# CPU.net
KiCad netlist of a schematic drawn in Altium Designer
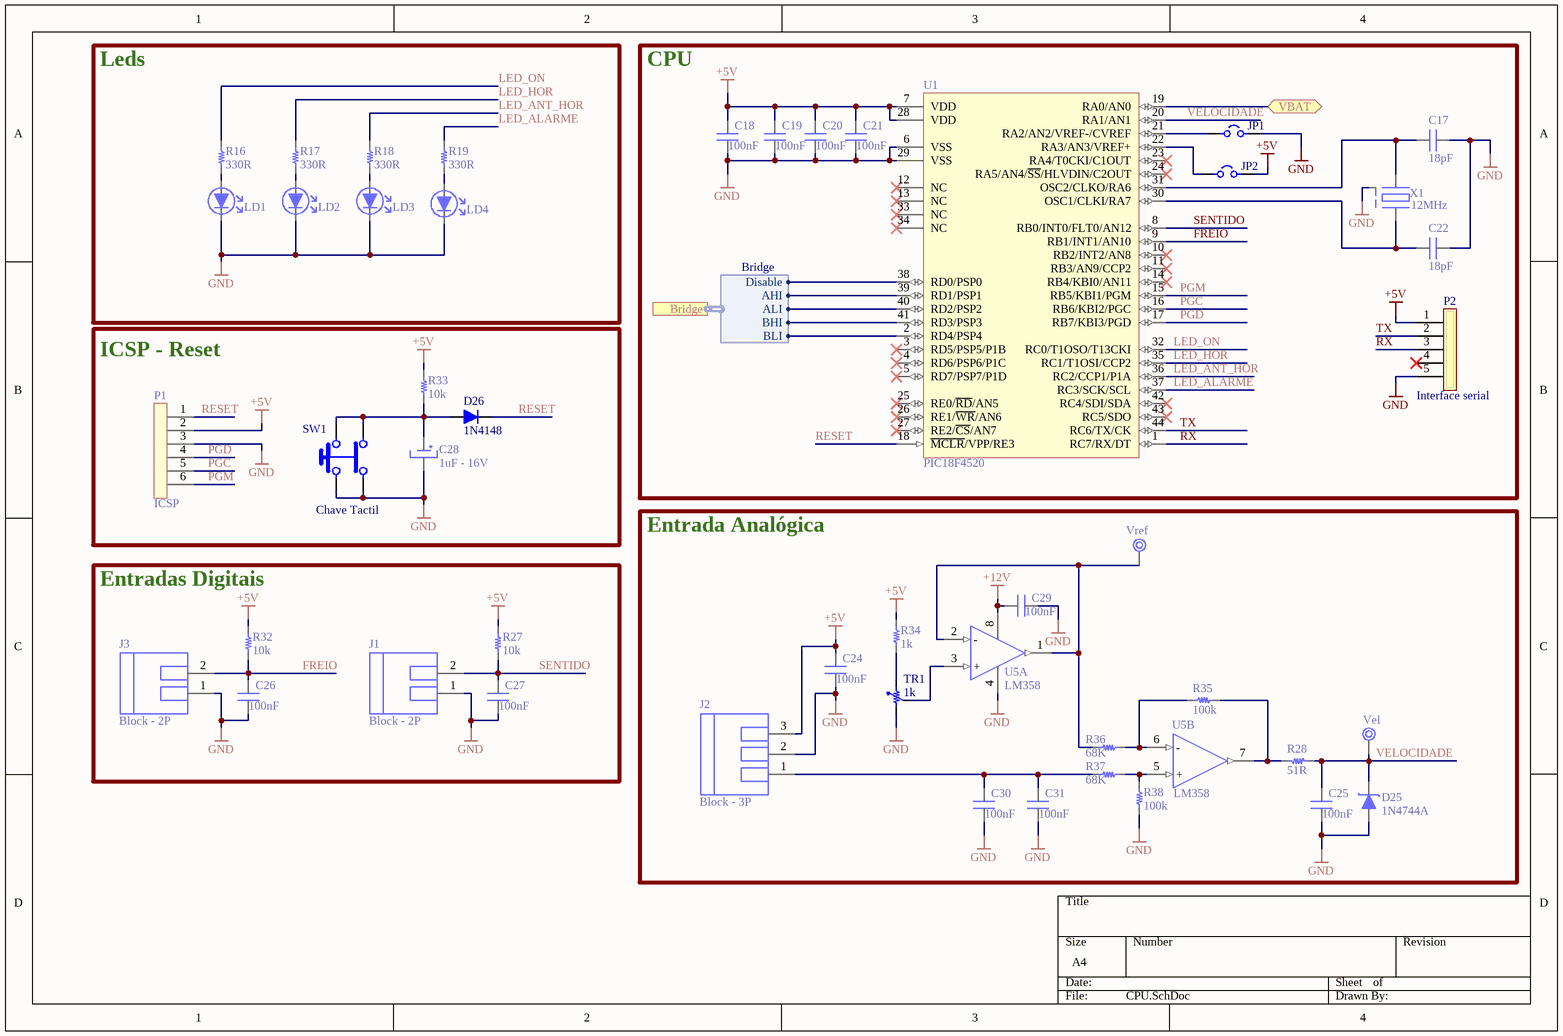
[diagram p0: CPU.SchDoc]

(export (version "E")
  (design (tool "Eeschema 10.0.6"))
  (components
    (comp (ref "C17")
      (value "18pF")
      (footprint "Capacitor_0805")
      (description "Capacitor C0805 18pF")
      (libsource (lib "bike") (part "Cap0805_100nF"))
    )
    (comp (ref "C18")
      (value "100nF")
      (footprint "Capacitor_0805")
      (description "Capacitor C0805 100nF Desacoplamento")
      (libsource (lib "bike") (part "Cap0805_100nF"))
    )
    (comp (ref "C19")
      (value "100nF")
      (footprint "Capacitor_0805")
      (description "Capacitor C0805 100nF Desacoplamento")
      (libsource (lib "bike") (part "Cap0805_100nF"))
    )
    (comp (ref "C20")
      (value "100nF")
      (footprint "Capacitor_0805")
      (description "Capacitor C0805 100nF Desacoplamento")
      (libsource (lib "bike") (part "Cap0805_100nF"))
    )
    (comp (ref "C21")
      (value "100nF")
      (footprint "Capacitor_0805")
      (description "Capacitor C0805 100nF Desacoplamento")
      (libsource (lib "bike") (part "Cap0805_100nF"))
    )
    (comp (ref "C22")
      (value "18pF")
      (footprint "Capacitor_0805")
      (description "Capacitor C0805 18pF")
      (libsource (lib "bike") (part "Cap0805_100nF"))
    )
    (comp (ref "C24")
      (value "100nF")
      (footprint "Capacitor_0805")
      (description "Capacitor C0805 100nF Desacoplamento")
      (libsource (lib "bike") (part "Cap0805_100nF"))
    )
    (comp (ref "C25")
      (value "100nF")
      (footprint "Capacitor_0805")
      (description "Capacitor C0805 100nF Desacoplamento")
      (libsource (lib "bike") (part "Cap0805_100nF"))
    )
    (comp (ref "C26")
      (value "100nF")
      (footprint "Capacitor_0805")
      (description "Capacitor C0805 100nF Desacoplamento")
      (libsource (lib "bike") (part "Cap0805_100nF"))
    )
    (comp (ref "C27")
      (value "100nF")
      (footprint "Capacitor_0805")
      (description "Capacitor C0805 100nF Desacoplamento")
      (libsource (lib "bike") (part "Cap0805_100nF"))
    )
    (comp (ref "C28")
      (value "1uF - 16V")
      (footprint "CAP_8x5mm")
      (description "Capacitor_1uF_16V")
      (libsource (lib "bike") (part "1uF - 16V"))
    )
    (comp (ref "C29")
      (value "100nF")
      (footprint "Capacitor_0805")
      (description "Capacitor C0805 100nF Desacoplamento")
      (libsource (lib "bike") (part "Cap0805_100nF"))
    )
    (comp (ref "C30")
      (value "100nF")
      (footprint "Capacitor_0805")
      (description "Capacitor C0805 100nF Desacoplamento")
      (libsource (lib "bike") (part "Cap0805_100nF"))
    )
    (comp (ref "C31")
      (value "100nF")
      (footprint "Capacitor_0805")
      (description "Capacitor C0805 100nF Desacoplamento")
      (libsource (lib "bike") (part "Cap0805_100nF"))
    )
    (comp (ref "D25")
      (value "1N4744A")
      (footprint "Diode_PHT")
      (description "Diodo Zener 15V 200mA")
      (libsource (lib "bike") (part "1N4744A"))
    )
    (comp (ref "D26")
      (value "1N4148")
      (footprint "SOD-80")
      (description "Diodo de uso geral")
      (libsource (lib "bike") (part "1N4148"))
    )
    (comp (ref "J1")
      (value "Block - 2P")
      (footprint "CONECTOR_2P_2PARTES")
      (description "Conector block 2 pinos 2 peças")
      (libsource (lib "bike") (part "Block - 2P"))
    )
    (comp (ref "J2")
      (value "Block - 3P")
      (footprint "CONECTOR_3P_2PARTES")
      (description "Conector block 3 pinos 2 peças")
      (libsource (lib "bike") (part "Block - 3P"))
    )
    (comp (ref "J3")
      (value "Block - 2P")
      (footprint "CONECTOR_2P_2PARTES")
      (description "Conector block 2 pinos 2 peças")
      (libsource (lib "bike") (part "Block - 2P"))
    )
    (comp (ref "JP1")
      (value "Jumper")
      (footprint "JUMPER")
      (description "Jumper de solda")
      (libsource (lib "bike") (part "Jumper"))
    )
    (comp (ref "JP2")
      (value "Jumper")
      (footprint "JUMPER")
      (description "Jumper de solda")
      (libsource (lib "bike") (part "Jumper"))
    )
    (comp (ref "LD1")
      (value "Led")
      (footprint "Led 5mm")
      (description "Led padrão PTH ou SMD")
      (libsource (lib "bike") (part "Led"))
    )
    (comp (ref "LD2")
      (value "Led")
      (footprint "Led 5mm")
      (description "Led padrão PTH ou SMD")
      (libsource (lib "bike") (part "Led"))
    )
    (comp (ref "LD3")
      (value "Led")
      (footprint "Led 5mm")
      (description "Led padrão PTH ou SMD")
      (libsource (lib "bike") (part "Led"))
    )
    (comp (ref "LD4")
      (value "Led")
      (footprint "Led 5mm")
      (description "Led padrão PTH ou SMD")
      (libsource (lib "bike") (part "Led"))
    )
    (comp (ref "P1")
      (value "ICSP")
      (footprint "header 1x6")
      (description "Conector ICSP para programação e debugger do PIC")
      (libsource (lib "bike") (part "ICSP"))
    )
    (comp (ref "P2")
      (value "Interface serial")
      (footprint "HEADER 1X5")
      (description "Header 1x5 2.56mm")
      (libsource (lib "bike") (part "Header 1x5"))
    )
    (comp (ref "R16")
      (value "330R")
      (footprint "R_0805")
      (description "Resistor padrão 0805")
      (libsource (lib "bike") (part "Resistor_330R"))
    )
    (comp (ref "R17")
      (value "330R")
      (footprint "R_0805")
      (description "Resistor padrão 0805")
      (libsource (lib "bike") (part "Resistor_330R"))
    )
    (comp (ref "R18")
      (value "330R")
      (footprint "R_0805")
      (description "Resistor padrão 0805")
      (libsource (lib "bike") (part "Resistor_330R"))
    )
    (comp (ref "R19")
      (value "330R")
      (footprint "R_0805")
      (description "Resistor padrão 0805")
      (libsource (lib "bike") (part "Resistor_330R"))
    )
    (comp (ref "R27")
      (value "10k")
      (footprint "R_0805")
      (description "Resistor padrão 0805")
      (libsource (lib "bike") (part "Resistor_10K"))
    )
    (comp (ref "R28")
      (value "51R")
      (footprint "R_0805")
      (description "Resistor padrão 0805")
      (libsource (lib "bike") (part "Resistor_10K"))
    )
    (comp (ref "R32")
      (value "10k")
      (footprint "R_0805")
      (description "Resistor padrão 0805")
      (libsource (lib "bike") (part "Resistor_10K"))
    )
    (comp (ref "R33")
      (value "10k")
      (footprint "R_0805")
      (description "Resistor padrão 0805")
      (libsource (lib "bike") (part "Resistor_10K"))
    )
    (comp (ref "R34")
      (value "1k")
      (footprint "R_0805")
      (description "Resistor padrão 0805")
      (libsource (lib "bike") (part "Resistor_10K"))
    )
    (comp (ref "R35")
      (value "100k")
      (footprint "R_0805")
      (description "Resistor padrão 0805")
      (libsource (lib "bike") (part "Resistor_10K"))
    )
    (comp (ref "R36")
      (value "68K")
      (footprint "R_0805")
      (description "Resistor padrão 0805")
      (libsource (lib "bike") (part "Resistor_10K"))
    )
    (comp (ref "R37")
      (value "68K")
      (footprint "R_0805")
      (description "Resistor padrão 0805")
      (libsource (lib "bike") (part "Resistor_10K"))
    )
    (comp (ref "R38")
      (value "100k")
      (footprint "R_0805")
      (description "Resistor padrão 0805")
      (libsource (lib "bike") (part "Resistor_10K"))
    )
    (comp (ref "SW1")
      (value "Chave Tactil")
      (footprint "CHAVE TACTIL")
      (description "Chave tactil")
      (libsource (lib "bike") (part "Chave Tactil"))
    )
    (comp (ref "TR1")
      (value "1k")
      (footprint "Trimpot")
      (description "Trimpot 1k")
      (libsource (lib "bike") (part "Trimpot"))
    )
    (comp (ref "U1")
      (value "PIC18F4520")
      (footprint "TQFP-PT44")
      (description "Microcontrolador de 8 bits da família PIC")
      (libsource (lib "bike") (part "PIC18F4520"))
    )
    (comp (ref "U5")
      (value "LM358")
      (footprint "SOP8")
      (description "LMx58-N Low-Power, Dual-Operational Amplifiers")
      (libsource (lib "bike") (part "LM358"))
    )
    (comp (ref "Vel") (value "+12V") (footprint "TEST_POINT") (libsource (lib "bike") (part "test_point")))
    (comp (ref "Vref") (value "+12V") (footprint "TEST_POINT") (libsource (lib "bike") (part "test_point")))
    (comp (ref "X1")
      (value "12MHz")
      (footprint "Crystal_3Pins - 4,98mm")
      (description "Crystal Genérico")
      (libsource (lib "bike") (part "Crystal"))
    )
  )
  (nets
    (net (code "2") (name "+5V") (class "Default")
      (node (ref "C18") (pin "2") (pinfunction "2_2") (pintype "passive"))
      (node (ref "C19") (pin "2") (pinfunction "2_2") (pintype "passive"))
      (node (ref "C20") (pin "2") (pinfunction "2_2") (pintype "passive"))
      (node (ref "C21") (pin "2") (pinfunction "2_2") (pintype "passive"))
      (node (ref "C24") (pin "2") (pinfunction "2_2") (pintype "passive"))
      (node (ref "J2") (pin "3") (pinfunction "3_3") (pintype "passive"))
      (node (ref "JP2") (pin "2") (pinfunction "2_2") (pintype "passive"))
      (node (ref "P1") (pin "2") (pinfunction "2_2") (pintype "passive"))
      (node (ref "P2") (pin "1") (pinfunction "1_1") (pintype "passive"))
      (node (ref "R27") (pin "2") (pinfunction "2_2") (pintype "passive"))
      (node (ref "R32") (pin "2") (pinfunction "2_2") (pintype "passive"))
      (node (ref "R33") (pin "2") (pinfunction "2_2") (pintype "passive"))
      (node (ref "R34") (pin "1") (pinfunction "1_1") (pintype "passive"))
      (node (ref "U1") (pin "28") (pinfunction "VDD_28") (pintype "power_in"))
      (node (ref "U1") (pin "7") (pinfunction "VDD_7") (pintype "power_in"))
    )
    (net (code "3") (name "+12V") (class "Default")
      (node (ref "C29") (pin "2") (pinfunction "2_2") (pintype "passive"))
      (node (ref "U5") (pin "8") (pinfunction "VCC_8") (pintype "passive"))
    )
    (net (code "4") (name "/AHI") (class "Default")
      (node (ref "U1") (pin "39") (pinfunction "RD1/PSP1_39") (pintype "bidirectional"))
    )
    (net (code "5") (name "/ALI") (class "Default")
      (node (ref "U1") (pin "40") (pinfunction "RD2/PSP2_40") (pintype "bidirectional"))
    )
    (net (code "6") (name "/BHI") (class "Default")
      (node (ref "U1") (pin "41") (pinfunction "RD3/PSP3_41") (pintype "bidirectional"))
    )
    (net (code "7") (name "/BLI") (class "Default")
      (node (ref "U1") (pin "2") (pinfunction "RD4/PSP4_2") (pintype "bidirectional"))
    )
    (net (code "8") (name "/Disable") (class "Default")
      (node (ref "U1") (pin "38") (pinfunction "RD0/PSP0_38") (pintype "bidirectional"))
    )
    (net (code "9") (name "/FREIO") (class "Default")
      (node (ref "C26") (pin "2") (pinfunction "2_2") (pintype "passive"))
      (node (ref "J3") (pin "2") (pinfunction "4_2") (pintype "passive"))
      (node (ref "R32") (pin "1") (pinfunction "1_1") (pintype "passive"))
      (node (ref "U1") (pin "9") (pinfunction "RB1/INT1/AN10_9") (pintype "bidirectional"))
    )
    (net (code "10") (name "/LED_ALARME") (class "Default")
      (node (ref "R19") (pin "2") (pinfunction "2_2") (pintype "passive"))
      (node (ref "U1") (pin "37") (pinfunction "RC3/SCK/SCL_37") (pintype "bidirectional"))
    )
    (net (code "11") (name "/LED_ANT_HOR") (class "Default")
      (node (ref "R18") (pin "2") (pinfunction "2_2") (pintype "passive"))
      (node (ref "U1") (pin "36") (pinfunction "RC2/CCP1/P1A_36") (pintype "bidirectional"))
    )
    (net (code "12") (name "/LED_HOR") (class "Default")
      (node (ref "R17") (pin "2") (pinfunction "2_2") (pintype "passive"))
      (node (ref "U1") (pin "35") (pinfunction "RC1/T1OSI/CCP2_35") (pintype "bidirectional"))
    )
    (net (code "13") (name "/LED_ON") (class "Default")
      (node (ref "R16") (pin "2") (pinfunction "2_2") (pintype "passive"))
      (node (ref "U1") (pin "32") (pinfunction "RC0/T1OSO/T13CKI_32") (pintype "bidirectional"))
    )
    (net (code "14") (name "/PGC") (class "Default")
      (node (ref "P1") (pin "5") (pinfunction "5_5") (pintype "passive"))
      (node (ref "U1") (pin "16") (pinfunction "RB6/KBI2/PGC_16") (pintype "bidirectional"))
    )
    (net (code "15") (name "/PGD") (class "Default")
      (node (ref "P1") (pin "4") (pinfunction "4_4") (pintype "passive"))
      (node (ref "U1") (pin "17") (pinfunction "RB7/KBI3/PGD_17") (pintype "bidirectional"))
    )
    (net (code "16") (name "/PGM") (class "Default")
      (node (ref "P1") (pin "6") (pinfunction "6_6") (pintype "passive"))
      (node (ref "U1") (pin "15") (pinfunction "RB5/KBI1/PGM_15") (pintype "bidirectional"))
    )
    (net (code "17") (name "/RESET") (class "Default")
      (node (ref "D26") (pin "1") (pinfunction "Catodo_1") (pintype "passive"))
      (node (ref "P1") (pin "1") (pinfunction "1_1") (pintype "passive"))
      (node (ref "U1") (pin "18") (pinfunction "~{MCLR}/VPP/RE3_18") (pintype "input"))
    )
    (net (code "18") (name "/RX") (class "Default")
      (node (ref "P2") (pin "3") (pinfunction "3_3") (pintype "passive"))
      (node (ref "U1") (pin "1") (pinfunction "RC7/RX/DT_1") (pintype "bidirectional"))
    )
    (net (code "19") (name "/SENTIDO") (class "Default")
      (node (ref "C27") (pin "2") (pinfunction "2_2") (pintype "passive"))
      (node (ref "J1") (pin "2") (pinfunction "4_2") (pintype "passive"))
      (node (ref "R27") (pin "1") (pinfunction "1_1") (pintype "passive"))
      (node (ref "U1") (pin "8") (pinfunction "RB0/INT0/FLT0/AN12_8") (pintype "bidirectional"))
    )
    (net (code "20") (name "/TX") (class "Default")
      (node (ref "P2") (pin "2") (pinfunction "2_2") (pintype "passive"))
      (node (ref "U1") (pin "44") (pinfunction "RC6/TX/CK_44") (pintype "bidirectional"))
    )
    (net (code "21") (name "/VBAT") (class "Default")
      (node (ref "U1") (pin "19") (pinfunction "RA0/AN0_19") (pintype "bidirectional"))
    )
    (net (code "22") (name "/VELOCIDADE") (class "Default")
      (node (ref "C25") (pin "2") (pinfunction "2_2") (pintype "passive"))
      (node (ref "D25") (pin "K") (pinfunction "Catodo_K") (pintype "passive"))
      (node (ref "R28") (pin "2") (pinfunction "2_2") (pintype "passive"))
      (node (ref "U1") (pin "20") (pinfunction "RA1/AN1_20") (pintype "bidirectional"))
      (node (ref "Vel") (pin "1") (pinfunction "1_1") (pintype "passive"))
    )
    (net (code "24") (name "GND") (class "Default")
      (node (ref "C17") (pin "1") (pinfunction "1_1") (pintype "passive"))
      (node (ref "C18") (pin "1") (pinfunction "1_1") (pintype "passive"))
      (node (ref "C19") (pin "1") (pinfunction "1_1") (pintype "passive"))
      (node (ref "C20") (pin "1") (pinfunction "1_1") (pintype "passive"))
      (node (ref "C21") (pin "1") (pinfunction "1_1") (pintype "passive"))
      (node (ref "C22") (pin "1") (pinfunction "1_1") (pintype "passive"))
      (node (ref "C24") (pin "1") (pinfunction "1_1") (pintype "passive"))
      (node (ref "C25") (pin "1") (pinfunction "1_1") (pintype "passive"))
      (node (ref "C26") (pin "1") (pinfunction "1_1") (pintype "passive"))
      (node (ref "C27") (pin "1") (pinfunction "1_1") (pintype "passive"))
      (node (ref "C28") (pin "2") (pinfunction "2_2") (pintype "passive"))
      (node (ref "C29") (pin "1") (pinfunction "1_1") (pintype "passive"))
      (node (ref "C30") (pin "1") (pinfunction "1_1") (pintype "passive"))
      (node (ref "C31") (pin "1") (pinfunction "1_1") (pintype "passive"))
      (node (ref "D25") (pin "A") (pinfunction "Anodo_A") (pintype "passive"))
      (node (ref "J1") (pin "1") (pinfunction "5_1") (pintype "passive"))
      (node (ref "J2") (pin "2") (pinfunction "4_2") (pintype "passive"))
      (node (ref "J3") (pin "1") (pinfunction "5_1") (pintype "passive"))
      (node (ref "JP1") (pin "2") (pinfunction "2_2") (pintype "passive"))
      (node (ref "LD1") (pin "1") (pinfunction "Catodo_1") (pintype "passive"))
      (node (ref "LD2") (pin "1") (pinfunction "Catodo_1") (pintype "passive"))
      (node (ref "LD3") (pin "1") (pinfunction "Catodo_1") (pintype "passive"))
      (node (ref "LD4") (pin "1") (pinfunction "Catodo_1") (pintype "passive"))
      (node (ref "P1") (pin "3") (pinfunction "3_3") (pintype "passive"))
      (node (ref "P2") (pin "5") (pinfunction "5_5") (pintype "passive"))
      (node (ref "R38") (pin "1") (pinfunction "1_1") (pintype "passive"))
      (node (ref "SW1") (pin "1") (pinfunction "1_1") (pintype "passive"))
      (node (ref "SW1") (pin "2") (pinfunction "2_2") (pintype "passive"))
      (node (ref "TR1") (pin "3") (pinfunction "3_3") (pintype "passive"))
      (node (ref "U1") (pin "29") (pinfunction "VSS_29") (pintype "power_in"))
      (node (ref "U1") (pin "6") (pinfunction "VSS_6") (pintype "power_in"))
      (node (ref "U5") (pin "4") (pinfunction "VDD_4") (pintype "passive"))
      (node (ref "X1") (pin "3") (pinfunction "GND_3") (pintype "passive"))
    )
    (net (code "25") (name "Net-(D26-Anodo)") (class "Default")
      (node (ref "C28") (pin "1") (pinfunction "1_1") (pintype "passive"))
      (node (ref "D26") (pin "2") (pinfunction "Anodo_2") (pintype "passive"))
      (node (ref "R33") (pin "1") (pinfunction "1_1") (pintype "passive"))
      (node (ref "SW1") (pin "3") (pinfunction "3_3") (pintype "passive"))
      (node (ref "SW1") (pin "4") (pinfunction "4_4") (pintype "passive"))
    )
    (net (code "26") (name "Net-(J2-5)") (class "Default")
      (node (ref "C30") (pin "2") (pinfunction "2_2") (pintype "passive"))
      (node (ref "C31") (pin "2") (pinfunction "2_2") (pintype "passive"))
      (node (ref "J2") (pin "1") (pinfunction "5_1") (pintype "passive"))
      (node (ref "R37") (pin "2") (pinfunction "2_2") (pintype "passive"))
    )
    (net (code "27") (name "Net-(LD1-Anodo)") (class "Default")
      (node (ref "LD1") (pin "2") (pinfunction "Anodo_2") (pintype "passive"))
      (node (ref "R16") (pin "1") (pinfunction "1_1") (pintype "passive"))
    )
    (net (code "28") (name "Net-(LD2-Anodo)") (class "Default")
      (node (ref "LD2") (pin "2") (pinfunction "Anodo_2") (pintype "passive"))
      (node (ref "R17") (pin "1") (pinfunction "1_1") (pintype "passive"))
    )
    (net (code "29") (name "Net-(LD3-Anodo)") (class "Default")
      (node (ref "LD3") (pin "2") (pinfunction "Anodo_2") (pintype "passive"))
      (node (ref "R18") (pin "1") (pinfunction "1_1") (pintype "passive"))
    )
    (net (code "30") (name "Net-(LD4-Anodo)") (class "Default")
      (node (ref "LD4") (pin "2") (pinfunction "Anodo_2") (pintype "passive"))
      (node (ref "R19") (pin "1") (pinfunction "1_1") (pintype "passive"))
    )
    (net (code "31") (name "Net-(R34-Pad2)") (class "Default")
      (node (ref "R34") (pin "2") (pinfunction "2_2") (pintype "passive"))
      (node (ref "TR1") (pin "1") (pinfunction "1_1") (pintype "passive"))
    )
    (net (code "32") (name "Net-(U1-OSC1{slash}CLKI{slash}RA7)") (class "Default")
      (node (ref "C22") (pin "2") (pinfunction "2_2") (pintype "passive"))
      (node (ref "U1") (pin "30") (pinfunction "OSC1/CLKI/RA7_30") (pintype "bidirectional"))
      (node (ref "X1") (pin "2") (pinfunction "2_2") (pintype "passive"))
    )
    (net (code "33") (name "Net-(U1-OSC2{slash}CLKO{slash}RA6)") (class "Default")
      (node (ref "C17") (pin "2") (pinfunction "2_2") (pintype "passive"))
      (node (ref "U1") (pin "31") (pinfunction "OSC2/CLKO/RA6_31") (pintype "bidirectional"))
      (node (ref "X1") (pin "1") (pinfunction "1_1") (pintype "passive"))
    )
    (net (code "34") (name "Net-(U1-RA2{slash}AN2{slash}VREF-{slash}CVREF)") (class "Default")
      (node (ref "JP1") (pin "1") (pinfunction "1_1") (pintype "passive"))
      (node (ref "U1") (pin "21") (pinfunction "RA2/AN2/VREF-/CVREF_21") (pintype "bidirectional"))
    )
    (net (code "35") (name "Net-(U1-RA3{slash}AN3{slash}VREF+)") (class "Default")
      (node (ref "JP2") (pin "1") (pinfunction "1_1") (pintype "passive"))
      (node (ref "U1") (pin "22") (pinfunction "RA3/AN3/VREF+_22") (pintype "bidirectional"))
    )
    (net (code "36") (name "Net-(U5A-+)") (class "Default")
      (node (ref "TR1") (pin "2") (pinfunction "2_2") (pintype "passive"))
      (node (ref "U5") (pin "3") (pinfunction "+_3") (pintype "input"))
    )
    (net (code "37") (name "Net-(U5A--)") (class "Default")
      (node (ref "R36") (pin "2") (pinfunction "2_2") (pintype "passive"))
      (node (ref "U5") (pin "1") (pinfunction "OUT-1_1") (pintype "output"))
      (node (ref "U5") (pin "2") (pinfunction "-_2") (pintype "input"))
      (node (ref "Vref") (pin "1") (pinfunction "1_1") (pintype "passive"))
    )
    (net (code "38") (name "Net-(U5B-+)") (class "Default")
      (node (ref "R37") (pin "1") (pinfunction "1_1") (pintype "passive"))
      (node (ref "R38") (pin "2") (pinfunction "2_2") (pintype "passive"))
      (node (ref "U5") (pin "5") (pinfunction "+_5") (pintype "input"))
    )
    (net (code "39") (name "Net-(U5B--)") (class "Default")
      (node (ref "R35") (pin "2") (pinfunction "2_2") (pintype "passive"))
      (node (ref "R36") (pin "1") (pinfunction "1_1") (pintype "passive"))
      (node (ref "U5") (pin "6") (pinfunction "-_6") (pintype "input"))
    )
    (net (code "40") (name "Net-(U5B-OUT-1)") (class "Default")
      (node (ref "R28") (pin "1") (pinfunction "1_1") (pintype "passive"))
      (node (ref "R35") (pin "1") (pinfunction "1_1") (pintype "passive"))
      (node (ref "U5") (pin "7") (pinfunction "OUT-1_7") (pintype "output"))
    )
    (net (code "41") (name "unconnected-(P2-Pad4)") (class "Default")
      (node (ref "P2") (pin "4") (pinfunction "4_4") (pintype "passive+no_connect"))
    )
    (net (code "42") (name "unconnected-(U1-NC-Pad12)") (class "Default")
      (node (ref "U1") (pin "12") (pinfunction "NC_12") (pintype "passive+no_connect"))
    )
    (net (code "43") (name "unconnected-(U1-NC-Pad13)") (class "Default")
      (node (ref "U1") (pin "13") (pinfunction "NC_13") (pintype "passive+no_connect"))
    )
    (net (code "44") (name "unconnected-(U1-NC-Pad33)") (class "Default")
      (node (ref "U1") (pin "33") (pinfunction "NC_33") (pintype "passive+no_connect"))
    )
    (net (code "45") (name "unconnected-(U1-NC-Pad34)") (class "Default")
      (node (ref "U1") (pin "34") (pinfunction "NC_34") (pintype "passive+no_connect"))
    )
    (net (code "46") (name "unconnected-(U1-RA4{slash}T0CKI{slash}C1OUT-Pad23)") (class "Default")
      (node (ref "U1") (pin "23") (pinfunction "RA4/T0CKI/C1OUT_23") (pintype "bidirectional+no_connect"))
    )
    (net (code "47") (name "unconnected-(U1-RA5{slash}AN4{slash}~{SS}{slash}HLVDIN{slash}C2OUT-Pad24)") (class "Default")
      (node (ref "U1") (pin "24") (pinfunction "RA5/AN4/~{SS}/HLVDIN/C2OUT_24") (pintype "bidirectional+no_connect"))
    )
    (net (code "48") (name "unconnected-(U1-RB2{slash}INT2{slash}AN8-Pad10)") (class "Default")
      (node (ref "U1") (pin "10") (pinfunction "RB2/INT2/AN8_10") (pintype "bidirectional+no_connect"))
    )
    (net (code "49") (name "unconnected-(U1-RB3{slash}AN9{slash}CCP2-Pad11)") (class "Default")
      (node (ref "U1") (pin "11") (pinfunction "RB3/AN9/CCP2_11") (pintype "bidirectional+no_connect"))
    )
    (net (code "50") (name "unconnected-(U1-RB4{slash}KBI0{slash}AN11-Pad14)") (class "Default")
      (node (ref "U1") (pin "14") (pinfunction "RB4/KBI0/AN11_14") (pintype "bidirectional+no_connect"))
    )
    (net (code "51") (name "unconnected-(U1-RC4{slash}SDI{slash}SDA-Pad42)") (class "Default")
      (node (ref "U1") (pin "42") (pinfunction "RC4/SDI/SDA_42") (pintype "bidirectional+no_connect"))
    )
    (net (code "52") (name "unconnected-(U1-RC5{slash}SDO-Pad43)") (class "Default")
      (node (ref "U1") (pin "43") (pinfunction "RC5/SDO_43") (pintype "bidirectional+no_connect"))
    )
    (net (code "53") (name "unconnected-(U1-RD5{slash}PSP5{slash}P1B-Pad3)") (class "Default")
      (node (ref "U1") (pin "3") (pinfunction "RD5/PSP5/P1B_3") (pintype "bidirectional+no_connect"))
    )
    (net (code "54") (name "unconnected-(U1-RD6{slash}PSP6{slash}P1C-Pad4)") (class "Default")
      (node (ref "U1") (pin "4") (pinfunction "RD6/PSP6/P1C_4") (pintype "bidirectional+no_connect"))
    )
    (net (code "55") (name "unconnected-(U1-RD7{slash}PSP7{slash}P1D-Pad5)") (class "Default")
      (node (ref "U1") (pin "5") (pinfunction "RD7/PSP7/P1D_5") (pintype "bidirectional+no_connect"))
    )
    (net (code "56") (name "unconnected-(U1-RE0{slash}~{RD}{slash}AN5-Pad25)") (class "Default")
      (node (ref "U1") (pin "25") (pinfunction "RE0/~{RD}/AN5_25") (pintype "bidirectional+no_connect"))
    )
    (net (code "57") (name "unconnected-(U1-RE1{slash}~{WR}{slash}AN6-Pad26)") (class "Default")
      (node (ref "U1") (pin "26") (pinfunction "RE1/~{WR}/AN6_26") (pintype "bidirectional+no_connect"))
    )
    (net (code "58") (name "unconnected-(U1-RE2{slash}~{CS}{slash}AN7-Pad27)") (class "Default")
      (node (ref "U1") (pin "27") (pinfunction "RE2/~{CS}/AN7_27") (pintype "bidirectional+no_connect"))
    )
  )
)
